# SCH_minir2.net
KiCad netlist of a schematic drawn in EasyEDA
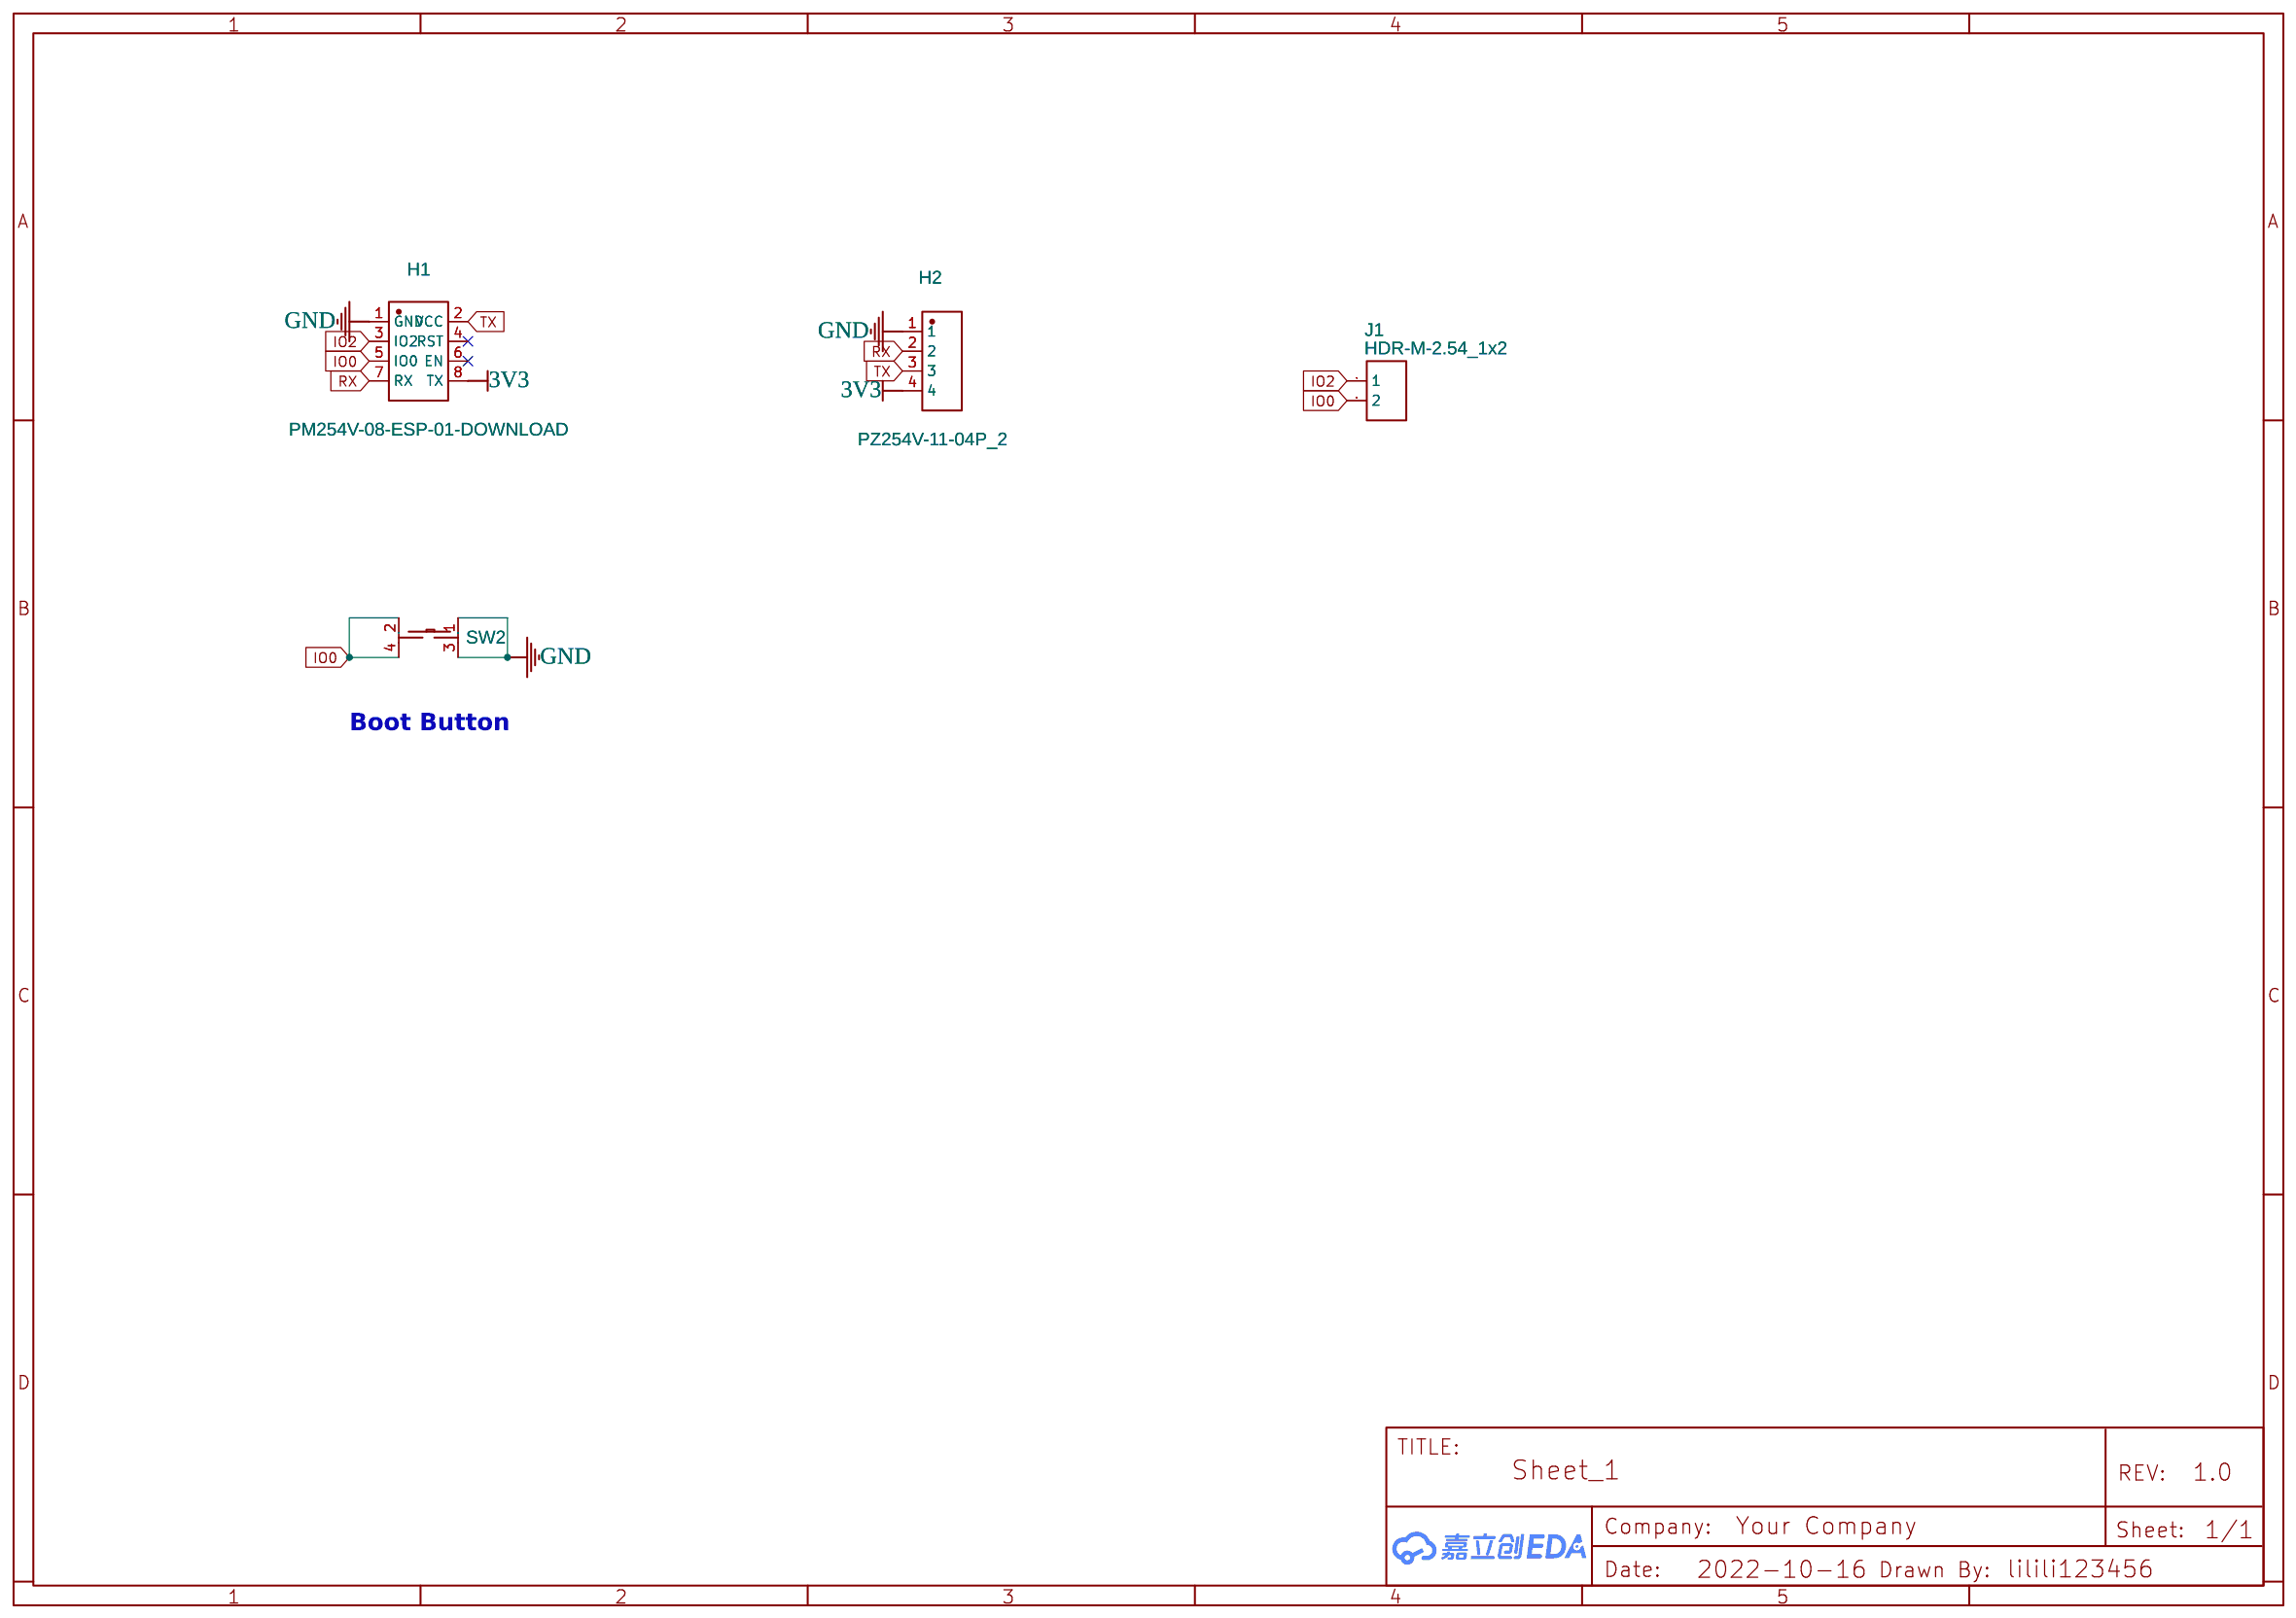
[diagram p0: schematic sheet]

(export (version "E")
  (design (tool "Eeschema 10.0.6"))
  (components
    (comp (ref "H1")
      (value "PM254V-08-ESP-01-DOWNLOAD")
      (fields
        (field (name "BOM_Manufacturer Part") "PM254V-12-08-H85")
        (field (name "BOM_Supplier Part") "C2834799")
      )
      (libsource (lib "") (part "PM254V-08-ESP-01-DOWNLOAD"))
    )
    (comp (ref "H2")
      (value "PZ254V-11-04P_2")
      (fields
        (field (name "BOM_Manufacturer Part") "PZ254V-11-04P")
        (field (name "BOM_Supplier Part") "C2691448")
      )
      (libsource (lib "") (part "PZ254V-11-04P_2"))
    )
    (comp (ref "J1")
      (value "HDR-M-2.54_1x2")
      (fields (field (name "BOM_Supplier Part") "C124375"))
      (libsource (lib "") (part "HDR-M-2.54_1x2"))
    )
    (comp (ref "SW2")
      (value "K2-1849SN-A3DW-06_LL")
      (fields
        (field (name "BOM_Manufacturer Part") "K2-1849SN-A3DW-06")
        (field (name "BOM_Supplier Part") "C442593")
      )
      (libsource (lib "") (part "K2-1849SN-A3DW-06_LL"))
    )
  )
  (nets
    (net (code "1") (name "3V3") (class "Default")
      (node (ref "H1") (pin "8") (pinfunction "TX_8") (pintype "unspecified"))
      (node (ref "H2") (pin "4") (pinfunction "4_4") (pintype "unspecified"))
    )
    (net (code "2") (name "GND") (class "Default")
      (node (ref "H1") (pin "1") (pinfunction "GND_1") (pintype "unspecified"))
      (node (ref "H2") (pin "1") (pinfunction "1_1") (pintype "unspecified"))
      (node (ref "SW2") (pin "1") (pinfunction "1_1") (pintype "unspecified"))
      (node (ref "SW2") (pin "3") (pinfunction "3_3") (pintype "unspecified"))
    )
    (net (code "3") (name "IO0") (class "Default")
      (node (ref "H1") (pin "5") (pinfunction "IO0_5") (pintype "unspecified"))
      (node (ref "J1") (pin "2") (pinfunction "2_2") (pintype "unspecified"))
      (node (ref "SW2") (pin "2") (pinfunction "2_2") (pintype "unspecified"))
      (node (ref "SW2") (pin "4") (pinfunction "4_4") (pintype "unspecified"))
    )
    (net (code "4") (name "IO2") (class "Default")
      (node (ref "H1") (pin "3") (pinfunction "IO2_3") (pintype "unspecified"))
      (node (ref "J1") (pin "1") (pinfunction "1_1") (pintype "unspecified"))
    )
    (net (code "5") (name "RX") (class "Default")
      (node (ref "H1") (pin "7") (pinfunction "RX_7") (pintype "unspecified"))
      (node (ref "H2") (pin "2") (pinfunction "2_2") (pintype "unspecified"))
    )
    (net (code "6") (name "TX") (class "Default")
      (node (ref "H1") (pin "2") (pinfunction "VCC_2") (pintype "unspecified"))
      (node (ref "H2") (pin "3") (pinfunction "3_3") (pintype "unspecified"))
    )
    (net (code "7") (name "unconnected-(H1-EN-Pad6)") (class "Default")
      (node (ref "H1") (pin "6") (pinfunction "EN_6") (pintype "unspecified+no_connect"))
    )
    (net (code "8") (name "unconnected-(H1-RST-Pad4)") (class "Default")
      (node (ref "H1") (pin "4") (pinfunction "RST_4") (pintype "unspecified+no_connect"))
    )
  )
)
